# Power_Supply_V4_1.net
KiCad netlist of a schematic drawn in EAGLE
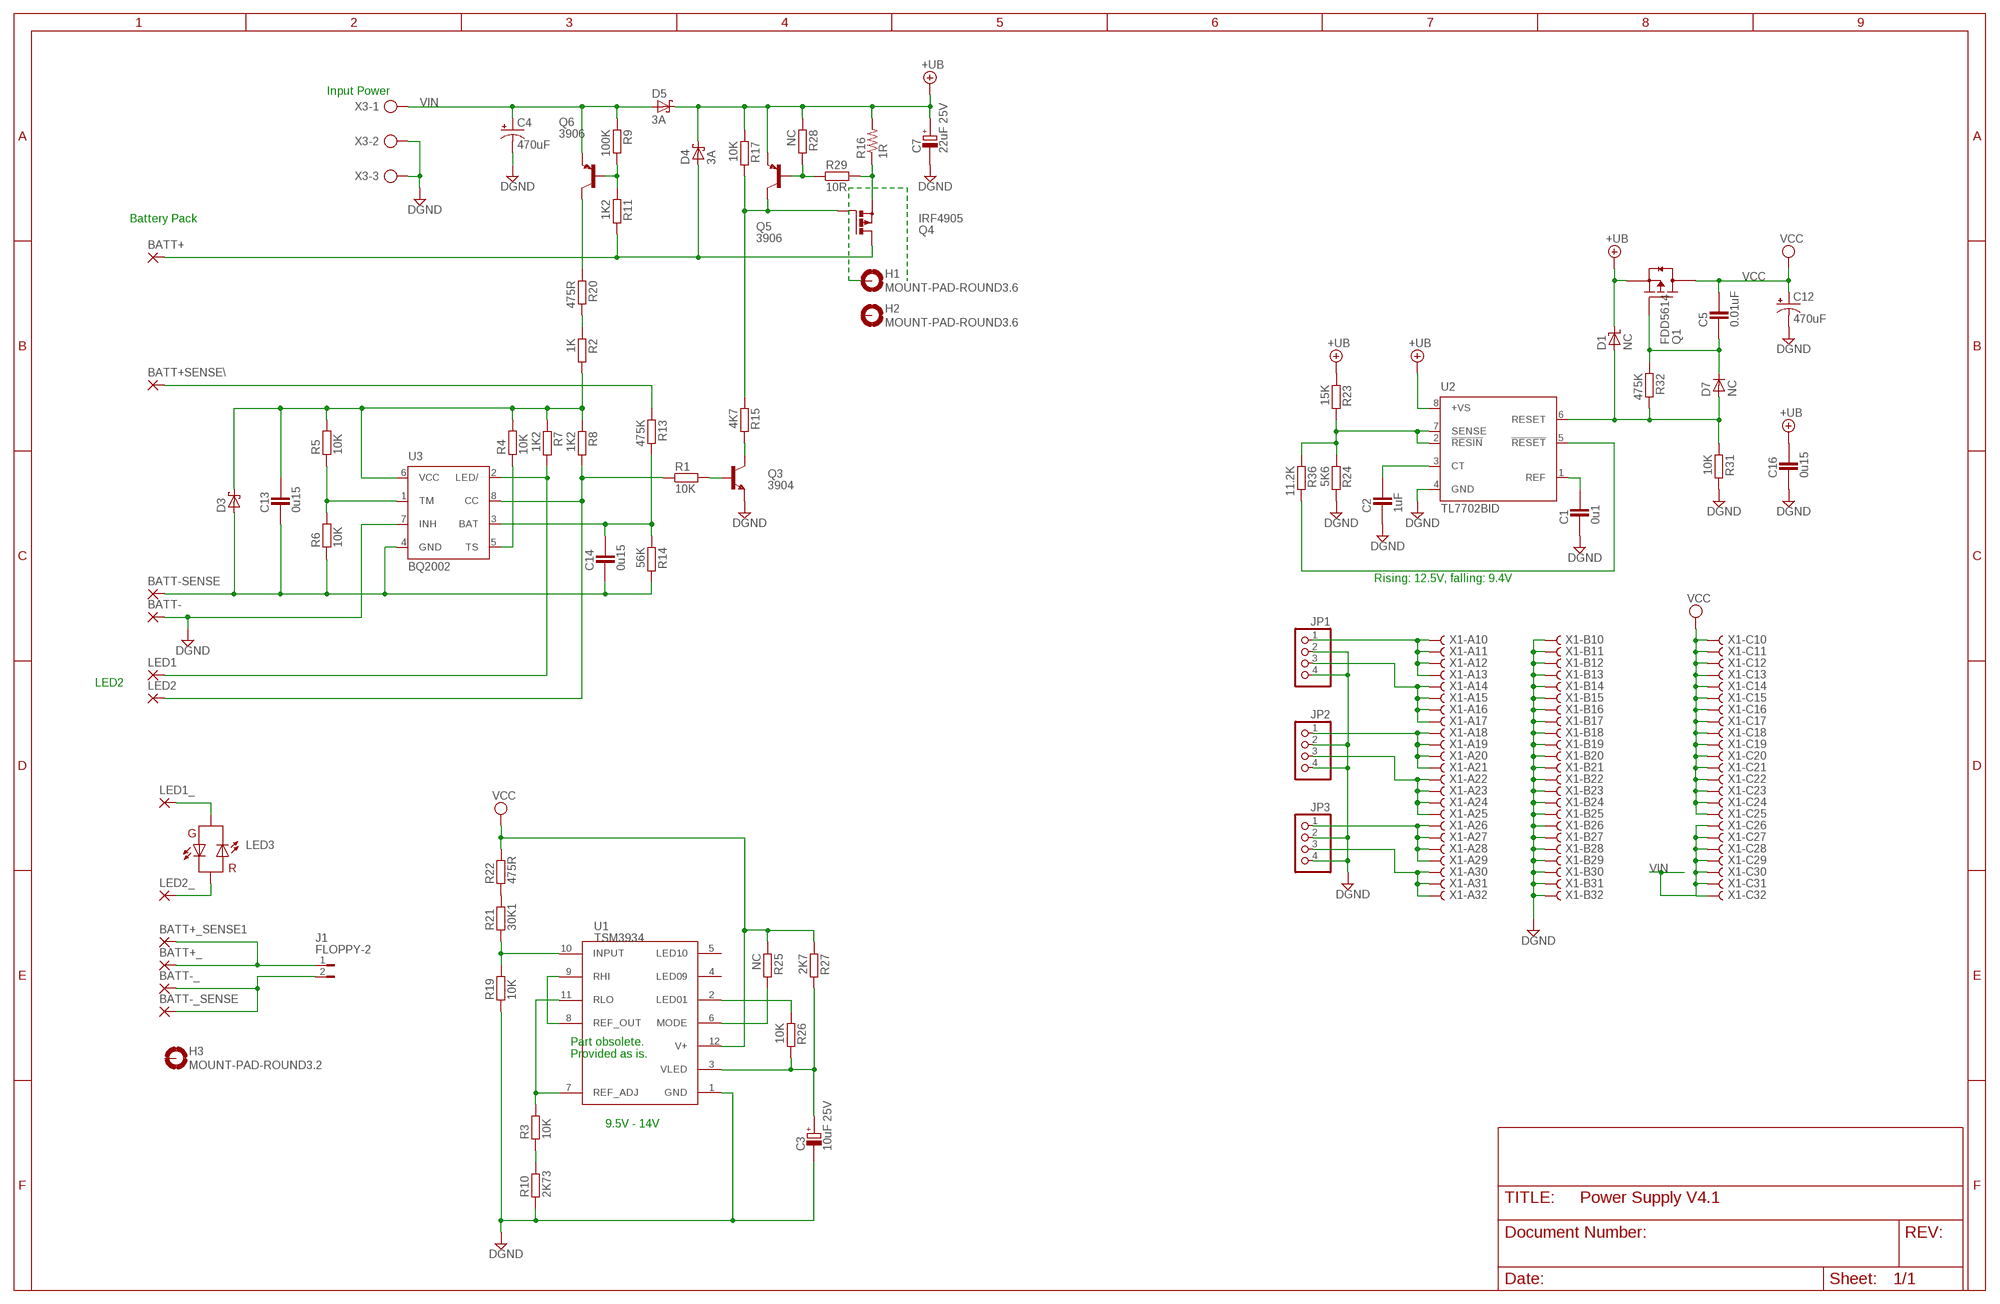
[diagram p0: schematic, sheet 1]

(export (version "E")
  (design (tool "Eeschema 10.0.6"))
  (components
    (comp (ref "BATT+")
      (value "SMD5")
      (footprint "eagle-import:SMD2,54-5,08")
      (libsource (lib "eagle-import") (part "SMD5"))
    )
    (comp (ref "BATT+SENSE\\")
      (value "SMD5")
      (footprint "eagle-import:SMD2,54-5,08")
      (libsource (lib "eagle-import") (part "SMD5"))
    )
    (comp (ref "BATT+_")
      (value "SMD5")
      (footprint "eagle-import:SMD2,54-5,08")
      (libsource (lib "eagle-import") (part "SMD5"))
    )
    (comp (ref "BATT+_SENSE1")
      (value "SMD5")
      (footprint "eagle-import:SMD2,54-5,08")
      (libsource (lib "eagle-import") (part "SMD5"))
    )
    (comp (ref "BATT-")
      (value "SMD5")
      (footprint "eagle-import:SMD2,54-5,08")
      (libsource (lib "eagle-import") (part "SMD5"))
    )
    (comp (ref "BATT-SENSE")
      (value "SMD5")
      (footprint "eagle-import:SMD2,54-5,08")
      (libsource (lib "eagle-import") (part "SMD5"))
    )
    (comp (ref "BATT-_")
      (value "SMD5")
      (footprint "eagle-import:SMD2,54-5,08")
      (libsource (lib "eagle-import") (part "SMD5"))
    )
    (comp (ref "BATT-_SENSE")
      (value "SMD5")
      (footprint "eagle-import:SMD2,54-5,08")
      (libsource (lib "eagle-import") (part "SMD5"))
    )
    (comp (ref "C1")
      (value "0u1")
      (footprint "eagle-import:CAPC1608X92N")
      (libsource (lib "eagle-import") (part "CAPACITOR_0603"))
    )
    (comp (ref "C2")
      (value "1uF")
      (footprint "eagle-import:CAPC1608X92N")
      (libsource (lib "eagle-import") (part "CAPACITOR_0603"))
    )
    (comp (ref "C3")
      (value "10uF 25V")
      (footprint "eagle-import:CAPMP7343X310N")
      (libsource (lib "eagle-import") (part "POLARISED_D_CASE"))
    )
    (comp (ref "C4")
      (value "470uF")
      (footprint "eagle-import:PANASONIC_G")
      (libsource (lib "eagle-import") (part "CAP_POLG"))
    )
    (comp (ref "C5")
      (value "0.01uF")
      (footprint "eagle-import:CAP2012X70N")
      (libsource (lib "eagle-import") (part "CAPACITOR_0805N"))
    )
    (comp (ref "C7")
      (value "22uF 25V")
      (footprint "eagle-import:CAPMP7343X310N")
      (libsource (lib "eagle-import") (part "POLARISED_D_CASE"))
    )
    (comp (ref "C12")
      (value "470uF")
      (footprint "eagle-import:PANASONIC_G")
      (libsource (lib "eagle-import") (part "CAP_POLG"))
    )
    (comp (ref "C13")
      (value "0u15")
      (footprint "eagle-import:CAPC1608X92N")
      (libsource (lib "eagle-import") (part "CAPACITOR_0603"))
    )
    (comp (ref "C14")
      (value "0u15")
      (footprint "eagle-import:CAPC1608X92N")
      (libsource (lib "eagle-import") (part "CAPACITOR_0603"))
    )
    (comp (ref "C16")
      (value "0u15")
      (footprint "eagle-import:CAPC1608X92N")
      (libsource (lib "eagle-import") (part "CAPACITOR_0603"))
    )
    (comp (ref "D1")
      (value "NC")
      (footprint "eagle-import:SOT95P280X135-3N")
      (libsource (lib "eagle-import") (part "ZENER_SOT-23"))
    )
    (comp (ref "D3")
      (value "SCHOTTKY_SOT-23")
      (footprint "eagle-import:SOT95P280X135-3N")
      (libsource (lib "eagle-import") (part "SCHOTTKY_SOT-23"))
    )
    (comp (ref "D4")
      (value "3A")
      (footprint "eagle-import:DIOM7959X265N")
      (libsource (lib "eagle-import") (part "SCHOTTKY_SMC"))
    )
    (comp (ref "D5")
      (value "3A")
      (footprint "eagle-import:DIOM7959X265N")
      (libsource (lib "eagle-import") (part "SCHOTTKY_SMC"))
    )
    (comp (ref "D7")
      (value "NC")
      (footprint "eagle-import:SOT95P280X135-3N")
      (libsource (lib "eagle-import") (part "DIODE_SOT-23"))
    )
    (comp (ref "H1")
      (value "MOUNT-PAD-ROUND3.6")
      (footprint "eagle-import:3,6-PAD")
      (libsource (lib "eagle-import") (part "MOUNT-PAD-ROUND3.6"))
    )
    (comp (ref "H2")
      (value "MOUNT-PAD-ROUND3.6")
      (footprint "eagle-import:3,6-PAD")
      (libsource (lib "eagle-import") (part "MOUNT-PAD-ROUND3.6"))
    )
    (comp (ref "H3")
      (value "MOUNT-PAD-ROUND3.2")
      (footprint "eagle-import:3,2-PAD")
      (libsource (lib "eagle-import") (part "MOUNT-PAD-ROUND3.2"))
    )
    (comp (ref "J1")
      (value "FLOPPY-2")
      (footprint "eagle-import:FLOPPY-2")
      (libsource (lib "eagle-import") (part "FLOPPY-2"))
    )
    (comp (ref "JP1")
      (value "PINHD-1X4_2.54")
      (footprint "eagle-import:1X04")
      (libsource (lib "eagle-import") (part "PINHD-1X4_2.54"))
    )
    (comp (ref "JP2")
      (value "PINHD-1X4_2.54")
      (footprint "eagle-import:1X04")
      (libsource (lib "eagle-import") (part "PINHD-1X4_2.54"))
    )
    (comp (ref "JP3")
      (value "PINHD-1X4_2.54")
      (footprint "eagle-import:1X04")
      (libsource (lib "eagle-import") (part "PINHD-1X4_2.54"))
    )
    (comp (ref "LED1")
      (value "SMD5")
      (footprint "eagle-import:SMD2,54-5,08")
      (libsource (lib "eagle-import") (part "SMD5"))
    )
    (comp (ref "LED1_")
      (value "SMD5")
      (footprint "eagle-import:SMD2,54-5,08")
      (libsource (lib "eagle-import") (part "SMD5"))
    )
    (comp (ref "LED2")
      (value "SMD5")
      (footprint "eagle-import:SMD2,54-5,08")
      (libsource (lib "eagle-import") (part "SMD5"))
    )
    (comp (ref "LED2_")
      (value "SMD5")
      (footprint "eagle-import:SMD2,54-5,08")
      (libsource (lib "eagle-import") (part "SMD5"))
    )
    (comp (ref "LED3")
      (value "DUAL-LED3MM")
      (footprint "eagle-import:LED3MM")
      (libsource (lib "eagle-import") (part "DUAL-LED3MM"))
    )
    (comp (ref "Q1")
      (value "FDD5614")
      (footprint "eagle-import:D-PAK_TO252AA")
      (libsource (lib "eagle-import") (part "MOSFET-PCH_D-PAK"))
    )
    (comp (ref "Q3")
      (value "3904")
      (footprint "eagle-import:SOT95P280X135-3N")
      (libsource (lib "eagle-import") (part "NPN_SOT-23"))
    )
    (comp (ref "Q4")
      (value "IRF4905")
      (footprint "eagle-import:TO220BH")
      (libsource (lib "eagle-import") (part "PMOSFET_PTO220BH"))
    )
    (comp (ref "Q5")
      (value "3906")
      (footprint "eagle-import:SOT95P280X135-3N")
      (libsource (lib "eagle-import") (part "PNP_SOT-23"))
    )
    (comp (ref "Q6")
      (value "3906")
      (footprint "eagle-import:SOT95P280X135-3N")
      (libsource (lib "eagle-import") (part "PNP_SOT-23"))
    )
    (comp (ref "R1")
      (value "10K")
      (footprint "eagle-import:RESC1608X55N")
      (libsource (lib "eagle-import") (part "RESISTOR_0603"))
    )
    (comp (ref "R2")
      (value "1K")
      (footprint "eagle-import:RESC2012X70N")
      (libsource (lib "eagle-import") (part "RESISTOR_0805"))
    )
    (comp (ref "R3")
      (value "10K")
      (footprint "eagle-import:RESC1608X55N")
      (libsource (lib "eagle-import") (part "RESISTOR_0603"))
    )
    (comp (ref "R4")
      (value "10K")
      (footprint "eagle-import:RESC1608X55N")
      (libsource (lib "eagle-import") (part "RESISTOR_0603"))
    )
    (comp (ref "R5")
      (value "10K")
      (footprint "eagle-import:RESC1608X55N")
      (libsource (lib "eagle-import") (part "RESISTOR_0603"))
    )
    (comp (ref "R6")
      (value "10K")
      (footprint "eagle-import:RESC1608X55N")
      (libsource (lib "eagle-import") (part "RESISTOR_0603"))
    )
    (comp (ref "R7")
      (value "1K2")
      (footprint "eagle-import:RESC1608X55N")
      (libsource (lib "eagle-import") (part "RESISTOR_0603"))
    )
    (comp (ref "R8")
      (value "1K2")
      (footprint "eagle-import:RESC1608X55N")
      (libsource (lib "eagle-import") (part "RESISTOR_0603"))
    )
    (comp (ref "R9")
      (value "100K")
      (footprint "eagle-import:RESC1608X55N")
      (libsource (lib "eagle-import") (part "RESISTOR_0603"))
    )
    (comp (ref "R10")
      (value "2K73")
      (footprint "eagle-import:RESC1608X55N")
      (libsource (lib "eagle-import") (part "RESISTOR_0603"))
    )
    (comp (ref "R11")
      (value "1K2")
      (footprint "eagle-import:RESC1608X55N")
      (libsource (lib "eagle-import") (part "RESISTOR_0603"))
    )
    (comp (ref "R13")
      (value "475K")
      (footprint "eagle-import:RESC1608X55N")
      (libsource (lib "eagle-import") (part "RESISTOR_0603"))
    )
    (comp (ref "R14")
      (value "56K")
      (footprint "eagle-import:RESC2012X70N")
      (libsource (lib "eagle-import") (part "RESISTOR_0805"))
    )
    (comp (ref "R15")
      (value "4K7")
      (footprint "eagle-import:RESC1608X55N")
      (libsource (lib "eagle-import") (part "RESISTOR_0603"))
    )
    (comp (ref "R16")
      (value "1R")
      (footprint "eagle-import:0411_12")
      (libsource (lib "eagle-import") (part "R-US_0411/12"))
    )
    (comp (ref "R17")
      (value "10K")
      (footprint "eagle-import:RESC1608X55N")
      (libsource (lib "eagle-import") (part "RESISTOR_0603"))
    )
    (comp (ref "R19")
      (value "10K")
      (footprint "eagle-import:RESC1608X55N")
      (libsource (lib "eagle-import") (part "RESISTOR_0603"))
    )
    (comp (ref "R20")
      (value "475R")
      (footprint "eagle-import:RESC2012X70N")
      (libsource (lib "eagle-import") (part "RESISTOR_0805"))
    )
    (comp (ref "R21")
      (value "30K1")
      (footprint "eagle-import:RESC1608X55N")
      (libsource (lib "eagle-import") (part "RESISTOR_0603"))
    )
    (comp (ref "R22")
      (value "475R")
      (footprint "eagle-import:RESC1608X55N")
      (libsource (lib "eagle-import") (part "RESISTOR_0603"))
    )
    (comp (ref "R23")
      (value "15K")
      (footprint "eagle-import:RESC2012X70N")
      (libsource (lib "eagle-import") (part "RESISTOR_0805"))
    )
    (comp (ref "R24")
      (value "5K6")
      (footprint "eagle-import:RESC2012X70N")
      (libsource (lib "eagle-import") (part "RESISTOR_0805"))
    )
    (comp (ref "R25")
      (value "NC")
      (footprint "eagle-import:RESC1608X55N")
      (libsource (lib "eagle-import") (part "RESISTOR_0603"))
    )
    (comp (ref "R26")
      (value "10K")
      (footprint "eagle-import:RESC1608X55N")
      (libsource (lib "eagle-import") (part "RESISTOR_0603"))
    )
    (comp (ref "R27")
      (value "2K7")
      (footprint "eagle-import:RESC1608X55N")
      (libsource (lib "eagle-import") (part "RESISTOR_0603"))
    )
    (comp (ref "R28")
      (value "NC")
      (footprint "eagle-import:RESC1608X55N")
      (libsource (lib "eagle-import") (part "RESISTOR_0603"))
    )
    (comp (ref "R29")
      (value "10R")
      (footprint "eagle-import:RESC1608X55N")
      (libsource (lib "eagle-import") (part "RESISTOR_0603"))
    )
    (comp (ref "R31")
      (value "10K")
      (footprint "eagle-import:RESC1608X55N")
      (libsource (lib "eagle-import") (part "RESISTOR_0603"))
    )
    (comp (ref "R32")
      (value "475K")
      (footprint "eagle-import:RESC1608X55N")
      (libsource (lib "eagle-import") (part "RESISTOR_0603"))
    )
    (comp (ref "R36")
      (value "11.2K")
      (footprint "eagle-import:RESC1608X55N")
      (libsource (lib "eagle-import") (part "RESISTOR_0603"))
    )
    (comp (ref "U1")
      (value "TSM3934")
      (footprint "eagle-import:TSM3934")
      (libsource (lib "eagle-import") (part "TSM3934"))
    )
    (comp (ref "U2")
      (value "TL7702BID")
      (footprint "eagle-import:SO08")
      (libsource (lib "eagle-import") (part "TL770D02AI"))
    )
    (comp (ref "U3")
      (value "BQ2002")
      (footprint "eagle-import:DIL08")
      (libsource (lib "eagle-import") (part "BQ2002TP"))
    )
    (comp (ref "X1")
      (value "FABC69R")
      (footprint "eagle-import:FABC69R")
      (libsource (lib "eagle-import") (part "FABC69R"))
    )
    (comp (ref "X3")
      (value "AK500/3")
      (footprint "eagle-import:AK500_3")
      (libsource (lib "eagle-import") (part "AK500/3"))
    )
  )
  (nets
    (net (code "1") (name "+UB") (class "Default")
      (node (ref "C16") (pin "2") (pinfunction "2_2") (pintype "passive"))
      (node (ref "C7") (pin "+") (pinfunction "+_+") (pintype "passive"))
      (node (ref "D1") (pin "3") (pinfunction "K_3") (pintype "passive"))
      (node (ref "D4") (pin "K") (pinfunction "K_K") (pintype "passive"))
      (node (ref "D5") (pin "K") (pinfunction "K_K") (pintype "passive"))
      (node (ref "Q1") (pin "3") (pinfunction "S_3") (pintype "passive"))
      (node (ref "Q5") (pin "2") (pinfunction "E_2") (pintype "passive"))
      (node (ref "R16") (pin "2") (pinfunction "2_2") (pintype "passive"))
      (node (ref "R17") (pin "1") (pinfunction "1_1") (pintype "passive"))
      (node (ref "R23") (pin "1") (pinfunction "1_1") (pintype "passive"))
      (node (ref "R28") (pin "1") (pinfunction "1_1") (pintype "passive"))
      (node (ref "U2") (pin "8") (pinfunction "+VS_8") (pintype "input"))
    )
    (net (code "2") (name "/VIN") (class "Default")
      (node (ref "C4") (pin "+") (pinfunction "+_+") (pintype "passive"))
      (node (ref "D5") (pin "A") (pinfunction "A_A") (pintype "passive"))
      (node (ref "Q6") (pin "2") (pinfunction "E_2") (pintype "passive"))
      (node (ref "R9") (pin "1") (pinfunction "1_1") (pintype "passive"))
      (node (ref "X1") (pin "C26") (pinfunction "B_C26") (pintype "passive"))
      (node (ref "X1") (pin "C27") (pinfunction "B_C27") (pintype "passive"))
      (node (ref "X1") (pin "C28") (pinfunction "B_C28") (pintype "passive"))
      (node (ref "X1") (pin "C29") (pinfunction "B_C29") (pintype "passive"))
      (node (ref "X1") (pin "C30") (pinfunction "B_C30") (pintype "passive"))
      (node (ref "X1") (pin "C31") (pinfunction "B_C31") (pintype "passive"))
      (node (ref "X1") (pin "C32") (pinfunction "B_C32") (pintype "passive"))
      (node (ref "X3") (pin "1") (pinfunction "KL_1") (pintype "passive"))
    )
    (net (code "3") (name "DGND") (class "Default")
      (node (ref "BATT-") (pin "1") (pinfunction "P_1") (pintype "passive"))
      (node (ref "C1") (pin "1") (pinfunction "1_1") (pintype "passive"))
      (node (ref "C12") (pin "-") (pinfunction "-_-") (pintype "passive"))
      (node (ref "C16") (pin "1") (pinfunction "1_1") (pintype "passive"))
      (node (ref "C2") (pin "1") (pinfunction "1_1") (pintype "passive"))
      (node (ref "C3") (pin "-") (pinfunction "-_-") (pintype "passive"))
      (node (ref "C4") (pin "-") (pinfunction "-_-") (pintype "passive"))
      (node (ref "C7") (pin "-") (pinfunction "-_-") (pintype "passive"))
      (node (ref "JP1") (pin "2") (pinfunction "2_2") (pintype "passive"))
      (node (ref "JP1") (pin "4") (pinfunction "4_4") (pintype "passive"))
      (node (ref "JP2") (pin "2") (pinfunction "2_2") (pintype "passive"))
      (node (ref "JP2") (pin "4") (pinfunction "4_4") (pintype "passive"))
      (node (ref "JP3") (pin "2") (pinfunction "2_2") (pintype "passive"))
      (node (ref "JP3") (pin "4") (pinfunction "4_4") (pintype "passive"))
      (node (ref "Q3") (pin "2") (pinfunction "E_2") (pintype "passive"))
      (node (ref "R10") (pin "1") (pinfunction "1_1") (pintype "passive"))
      (node (ref "R19") (pin "1") (pinfunction "1_1") (pintype "passive"))
      (node (ref "R24") (pin "2") (pinfunction "2_2") (pintype "passive"))
      (node (ref "R31") (pin "2") (pinfunction "2_2") (pintype "passive"))
      (node (ref "U1") (pin "1") (pinfunction "GND_1") (pintype "power_in"))
      (node (ref "U2") (pin "4") (pinfunction "GND_4") (pintype "power_in"))
      (node (ref "U3") (pin "7") (pinfunction "INH_7") (pintype "input"))
      (node (ref "X1") (pin "B10") (pinfunction "B_B10") (pintype "passive"))
      (node (ref "X1") (pin "B11") (pinfunction "B_B11") (pintype "passive"))
      (node (ref "X1") (pin "B12") (pinfunction "B_B12") (pintype "passive"))
      (node (ref "X1") (pin "B13") (pinfunction "B_B13") (pintype "passive"))
      (node (ref "X1") (pin "B14") (pinfunction "B_B14") (pintype "passive"))
      (node (ref "X1") (pin "B15") (pinfunction "B_B15") (pintype "passive"))
      (node (ref "X1") (pin "B16") (pinfunction "B_B16") (pintype "passive"))
      (node (ref "X1") (pin "B17") (pinfunction "B_B17") (pintype "passive"))
      (node (ref "X1") (pin "B18") (pinfunction "B_B18") (pintype "passive"))
      (node (ref "X1") (pin "B19") (pinfunction "B_B19") (pintype "passive"))
      (node (ref "X1") (pin "B20") (pinfunction "B_B20") (pintype "passive"))
      (node (ref "X1") (pin "B21") (pinfunction "B_B21") (pintype "passive"))
      (node (ref "X1") (pin "B22") (pinfunction "B_B22") (pintype "passive"))
      (node (ref "X1") (pin "B23") (pinfunction "B_B23") (pintype "passive"))
      (node (ref "X1") (pin "B24") (pinfunction "B_B24") (pintype "passive"))
      (node (ref "X1") (pin "B25") (pinfunction "B_B25") (pintype "passive"))
      (node (ref "X1") (pin "B26") (pinfunction "B_B26") (pintype "passive"))
      (node (ref "X1") (pin "B27") (pinfunction "B_B27") (pintype "passive"))
      (node (ref "X1") (pin "B28") (pinfunction "B_B28") (pintype "passive"))
      (node (ref "X1") (pin "B29") (pinfunction "B_B29") (pintype "passive"))
      (node (ref "X1") (pin "B30") (pinfunction "B_B30") (pintype "passive"))
      (node (ref "X1") (pin "B31") (pinfunction "B_B31") (pintype "passive"))
      (node (ref "X1") (pin "B32") (pinfunction "B_B32") (pintype "passive"))
      (node (ref "X3") (pin "2") (pinfunction "KL_2") (pintype "passive"))
      (node (ref "X3") (pin "3") (pinfunction "KL_3") (pintype "passive"))
    )
    (net (code "4") (name "Net-(BATT+-P)") (class "Default")
      (node (ref "BATT+") (pin "1") (pinfunction "P_1") (pintype "passive"))
      (node (ref "D4") (pin "A") (pinfunction "A_A") (pintype "passive"))
      (node (ref "Q4") (pin "D") (pinfunction "D_D") (pintype "passive"))
      (node (ref "R11") (pin "2") (pinfunction "2_2") (pintype "passive"))
    )
    (net (code "5") (name "Net-(BATT+SENSE\\-P)") (class "Default")
      (node (ref "BATT+SENSE\\") (pin "1") (pinfunction "P_1") (pintype "passive"))
      (node (ref "R13") (pin "1") (pinfunction "1_1") (pintype "passive"))
    )
    (net (code "6") (name "Net-(BATT+_-P)") (class "Default")
      (node (ref "BATT+_") (pin "1") (pinfunction "P_1") (pintype "passive"))
      (node (ref "BATT+_SENSE1") (pin "1") (pinfunction "P_1") (pintype "passive"))
      (node (ref "J1") (pin "1") (pinfunction "1_1") (pintype "passive"))
    )
    (net (code "7") (name "Net-(BATT-SENSE-P)") (class "Default")
      (node (ref "BATT-SENSE") (pin "1") (pinfunction "P_1") (pintype "passive"))
      (node (ref "C13") (pin "1") (pinfunction "1_1") (pintype "passive"))
      (node (ref "C14") (pin "1") (pinfunction "1_1") (pintype "passive"))
      (node (ref "D3") (pin "1") (pinfunction "A_1") (pintype "passive"))
      (node (ref "R14") (pin "2") (pinfunction "2_2") (pintype "passive"))
      (node (ref "R6") (pin "1") (pinfunction "1_1") (pintype "passive"))
      (node (ref "U3") (pin "4") (pinfunction "GND_4") (pintype "power_in"))
    )
    (net (code "8") (name "Net-(BATT-_-P)") (class "Default")
      (node (ref "BATT-_") (pin "1") (pinfunction "P_1") (pintype "passive"))
      (node (ref "BATT-_SENSE") (pin "1") (pinfunction "P_1") (pintype "passive"))
      (node (ref "J1") (pin "2") (pinfunction "2_2") (pintype "passive"))
    )
    (net (code "9") (name "Net-(D1-A)") (class "Default")
      (node (ref "D1") (pin "1") (pinfunction "A_1") (pintype "passive"))
      (node (ref "D7") (pin "1") (pinfunction "A_1") (pintype "passive"))
      (node (ref "R31") (pin "1") (pinfunction "1_1") (pintype "passive"))
      (node (ref "R32") (pin "2") (pinfunction "2_2") (pintype "passive"))
      (node (ref "U2") (pin "6") (pinfunction "RESET_6") (pintype "open_collector"))
    )
    (net (code "10") (name "Net-(D3-K)") (class "Default")
      (node (ref "C13") (pin "2") (pinfunction "2_2") (pintype "passive"))
      (node (ref "D3") (pin "3") (pinfunction "K_3") (pintype "passive"))
      (node (ref "R2") (pin "2") (pinfunction "2_2") (pintype "passive"))
      (node (ref "R4") (pin "2") (pinfunction "2_2") (pintype "passive"))
      (node (ref "R5") (pin "2") (pinfunction "2_2") (pintype "passive"))
      (node (ref "R7") (pin "1") (pinfunction "1_1") (pintype "passive"))
      (node (ref "R8") (pin "1") (pinfunction "1_1") (pintype "passive"))
      (node (ref "U3") (pin "6") (pinfunction "VCC_6") (pintype "power_in"))
    )
    (net (code "11") (name "Net-(D7-K)") (class "Default")
      (node (ref "C5") (pin "1") (pinfunction "1_1") (pintype "passive"))
      (node (ref "D7") (pin "3") (pinfunction "K_3") (pintype "passive"))
      (node (ref "Q1") (pin "1") (pinfunction "G_1") (pintype "passive"))
      (node (ref "R32") (pin "1") (pinfunction "1_1") (pintype "passive"))
    )
    (net (code "12") (name "Net-(LED1-P)") (class "Default")
      (node (ref "LED1") (pin "1") (pinfunction "P_1") (pintype "passive"))
      (node (ref "R7") (pin "2") (pinfunction "2_2") (pintype "passive"))
      (node (ref "U3") (pin "2") (pinfunction "LED/_2") (pintype "open_collector"))
    )
    (net (code "13") (name "Net-(LED1_-P)") (class "Default")
      (node (ref "LED1_") (pin "1") (pinfunction "P_1") (pintype "passive"))
      (node (ref "LED3") (pin "A") (pinfunction "A_A") (pintype "passive"))
    )
    (net (code "14") (name "Net-(LED2-P)") (class "Default")
      (node (ref "LED2") (pin "1") (pinfunction "P_1") (pintype "passive"))
      (node (ref "R1") (pin "1") (pinfunction "1_1") (pintype "passive"))
      (node (ref "R8") (pin "2") (pinfunction "2_2") (pintype "passive"))
      (node (ref "U3") (pin "8") (pinfunction "CC_8") (pintype "open_collector"))
    )
    (net (code "15") (name "Net-(LED2_-P)") (class "Default")
      (node (ref "LED2_") (pin "1") (pinfunction "P_1") (pintype "passive"))
      (node (ref "LED3") (pin "K") (pinfunction "C_K") (pintype "passive"))
    )
    (net (code "16") (name "Net-(Q3-B)") (class "Default")
      (node (ref "Q3") (pin "1") (pinfunction "B_1") (pintype "passive"))
      (node (ref "R1") (pin "2") (pinfunction "2_2") (pintype "passive"))
    )
    (net (code "17") (name "Net-(Q3-C)") (class "Default")
      (node (ref "Q3") (pin "3") (pinfunction "C_3") (pintype "passive"))
      (node (ref "R15") (pin "2") (pinfunction "2_2") (pintype "passive"))
    )
    (net (code "18") (name "Net-(Q4-PadS)") (class "Default")
      (node (ref "Q4") (pin "S") (pinfunction "S_S") (pintype "passive"))
      (node (ref "R16") (pin "1") (pinfunction "1_1") (pintype "passive"))
      (node (ref "R29") (pin "2") (pinfunction "2_2") (pintype "passive"))
    )
    (net (code "19") (name "Net-(Q5-B)") (class "Default")
      (node (ref "Q5") (pin "1") (pinfunction "B_1") (pintype "passive"))
      (node (ref "R28") (pin "2") (pinfunction "2_2") (pintype "passive"))
      (node (ref "R29") (pin "1") (pinfunction "1_1") (pintype "passive"))
    )
    (net (code "20") (name "Net-(Q5-C)") (class "Default")
      (node (ref "Q4") (pin "G") (pinfunction "G_G") (pintype "passive"))
      (node (ref "Q5") (pin "3") (pinfunction "C_3") (pintype "passive"))
      (node (ref "R15") (pin "1") (pinfunction "1_1") (pintype "passive"))
      (node (ref "R17") (pin "2") (pinfunction "2_2") (pintype "passive"))
    )
    (net (code "21") (name "Net-(Q6-B)") (class "Default")
      (node (ref "Q6") (pin "1") (pinfunction "B_1") (pintype "passive"))
      (node (ref "R11") (pin "1") (pinfunction "1_1") (pintype "passive"))
      (node (ref "R9") (pin "2") (pinfunction "2_2") (pintype "passive"))
    )
    (net (code "22") (name "Net-(Q6-C)") (class "Default")
      (node (ref "Q6") (pin "3") (pinfunction "C_3") (pintype "passive"))
      (node (ref "R20") (pin "1") (pinfunction "1_1") (pintype "passive"))
    )
    (net (code "23") (name "Net-(R2-Pad1)") (class "Default")
      (node (ref "R2") (pin "1") (pinfunction "1_1") (pintype "passive"))
      (node (ref "R20") (pin "2") (pinfunction "2_2") (pintype "passive"))
    )
    (net (code "24") (name "Net-(R10-Pad2)") (class "Default")
      (node (ref "R10") (pin "2") (pinfunction "2_2") (pintype "passive"))
      (node (ref "R3") (pin "1") (pinfunction "1_1") (pintype "passive"))
    )
    (net (code "25") (name "Net-(R21-Pad2)") (class "Default")
      (node (ref "R21") (pin "2") (pinfunction "2_2") (pintype "passive"))
      (node (ref "R22") (pin "1") (pinfunction "1_1") (pintype "passive"))
    )
    (net (code "26") (name "Net-(U1-INPUT)") (class "Default")
      (node (ref "R19") (pin "2") (pinfunction "2_2") (pintype "passive"))
      (node (ref "R21") (pin "1") (pinfunction "1_1") (pintype "passive"))
      (node (ref "U1") (pin "10") (pinfunction "INPUT_10") (pintype "input"))
    )
    (net (code "27") (name "Net-(U1-LED01)") (class "Default")
      (node (ref "R26") (pin "1") (pinfunction "1_1") (pintype "passive"))
      (node (ref "U1") (pin "2") (pinfunction "LED01_2") (pintype "output"))
    )
    (net (code "28") (name "Net-(U1-MODE)") (class "Default")
      (node (ref "R25") (pin "2") (pinfunction "2_2") (pintype "passive"))
      (node (ref "U1") (pin "6") (pinfunction "MODE_6") (pintype "input"))
    )
    (net (code "29") (name "Net-(U1-REF_ADJ)") (class "Default")
      (node (ref "R3") (pin "2") (pinfunction "2_2") (pintype "passive"))
      (node (ref "U1") (pin "11") (pinfunction "RLO_11") (pintype "input"))
      (node (ref "U1") (pin "7") (pinfunction "REF_ADJ_7") (pintype "input"))
    )
    (net (code "30") (name "Net-(U1-REF_OUT)") (class "Default")
      (node (ref "U1") (pin "8") (pinfunction "REF_OUT_8") (pintype "output"))
      (node (ref "U1") (pin "9") (pinfunction "RHI_9") (pintype "input"))
    )
    (net (code "31") (name "Net-(U1-VLED)") (class "Default")
      (node (ref "C3") (pin "+") (pinfunction "+_+") (pintype "passive"))
      (node (ref "R26") (pin "2") (pinfunction "2_2") (pintype "passive"))
      (node (ref "R27") (pin "2") (pinfunction "2_2") (pintype "passive"))
      (node (ref "U1") (pin "3") (pinfunction "VLED_3") (pintype "power_in"))
    )
    (net (code "32") (name "Net-(U2-CT)") (class "Default")
      (node (ref "C2") (pin "2") (pinfunction "2_2") (pintype "passive"))
      (node (ref "U2") (pin "3") (pinfunction "CT_3") (pintype "input"))
    )
    (net (code "33") (name "Net-(U2-REF)") (class "Default")
      (node (ref "C1") (pin "2") (pinfunction "2_2") (pintype "passive"))
      (node (ref "U2") (pin "1") (pinfunction "REF_1") (pintype "input"))
    )
    (net (code "34") (name "Net-(U2-SENSE)") (class "Default")
      (node (ref "R23") (pin "2") (pinfunction "2_2") (pintype "passive"))
      (node (ref "R24") (pin "1") (pinfunction "1_1") (pintype "passive"))
      (node (ref "R36") (pin "1") (pinfunction "1_1") (pintype "passive"))
      (node (ref "U2") (pin "2") (pinfunction "~{RESIN}_2") (pintype "input"))
      (node (ref "U2") (pin "7") (pinfunction "SENSE_7") (pintype "input"))
    )
    (net (code "35") (name "Net-(U2-~{RESET})") (class "Default")
      (node (ref "R36") (pin "2") (pinfunction "2_2") (pintype "passive"))
      (node (ref "U2") (pin "5") (pinfunction "~{RESET}_5") (pintype "open_collector"))
    )
    (net (code "36") (name "Net-(U3-BAT)") (class "Default")
      (node (ref "C14") (pin "2") (pinfunction "2_2") (pintype "passive"))
      (node (ref "R13") (pin "2") (pinfunction "2_2") (pintype "passive"))
      (node (ref "R14") (pin "1") (pinfunction "1_1") (pintype "passive"))
      (node (ref "U3") (pin "3") (pinfunction "BAT_3") (pintype "input"))
    )
    (net (code "37") (name "Net-(U3-TM)") (class "Default")
      (node (ref "R5") (pin "1") (pinfunction "1_1") (pintype "passive"))
      (node (ref "R6") (pin "2") (pinfunction "2_2") (pintype "passive"))
      (node (ref "U3") (pin "1") (pinfunction "TM_1") (pintype "input"))
    )
    (net (code "38") (name "Net-(U3-TS)") (class "Default")
      (node (ref "R4") (pin "1") (pinfunction "1_1") (pintype "passive"))
      (node (ref "U3") (pin "5") (pinfunction "TS_5") (pintype "input"))
    )
    (net (code "39") (name "Net-(X1A-B)") (class "Default")
      (node (ref "JP1") (pin "1") (pinfunction "1_1") (pintype "passive"))
      (node (ref "X1") (pin "A10") (pinfunction "B_A10") (pintype "passive"))
      (node (ref "X1") (pin "A11") (pinfunction "B_A11") (pintype "passive"))
      (node (ref "X1") (pin "A12") (pinfunction "B_A12") (pintype "passive"))
      (node (ref "X1") (pin "A13") (pinfunction "B_A13") (pintype "passive"))
    )
    (net (code "40") (name "Net-(X1E-B)") (class "Default")
      (node (ref "JP1") (pin "3") (pinfunction "3_3") (pintype "passive"))
      (node (ref "X1") (pin "A14") (pinfunction "B_A14") (pintype "passive"))
      (node (ref "X1") (pin "A15") (pinfunction "B_A15") (pintype "passive"))
      (node (ref "X1") (pin "A16") (pinfunction "B_A16") (pintype "passive"))
      (node (ref "X1") (pin "A17") (pinfunction "B_A17") (pintype "passive"))
    )
    (net (code "41") (name "Net-(X1I-B)") (class "Default")
      (node (ref "JP2") (pin "1") (pinfunction "1_1") (pintype "passive"))
      (node (ref "X1") (pin "A18") (pinfunction "B_A18") (pintype "passive"))
      (node (ref "X1") (pin "A19") (pinfunction "B_A19") (pintype "passive"))
      (node (ref "X1") (pin "A20") (pinfunction "B_A20") (pintype "passive"))
      (node (ref "X1") (pin "A21") (pinfunction "B_A21") (pintype "passive"))
    )
    (net (code "42") (name "Net-(X1M-B)") (class "Default")
      (node (ref "JP2") (pin "3") (pinfunction "3_3") (pintype "passive"))
      (node (ref "X1") (pin "A22") (pinfunction "B_A22") (pintype "passive"))
      (node (ref "X1") (pin "A23") (pinfunction "B_A23") (pintype "passive"))
      (node (ref "X1") (pin "A24") (pinfunction "B_A24") (pintype "passive"))
      (node (ref "X1") (pin "A25") (pinfunction "B_A25") (pintype "passive"))
    )
    (net (code "43") (name "Net-(X1Q-B)") (class "Default")
      (node (ref "JP3") (pin "1") (pinfunction "1_1") (pintype "passive"))
      (node (ref "X1") (pin "A26") (pinfunction "B_A26") (pintype "passive"))
      (node (ref "X1") (pin "A27") (pinfunction "B_A27") (pintype "passive"))
      (node (ref "X1") (pin "A28") (pinfunction "B_A28") (pintype "passive"))
      (node (ref "X1") (pin "A29") (pinfunction "B_A29") (pintype "passive"))
    )
    (net (code "44") (name "Net-(X1U-B)") (class "Default")
      (node (ref "JP3") (pin "3") (pinfunction "3_3") (pintype "passive"))
      (node (ref "X1") (pin "A30") (pinfunction "B_A30") (pintype "passive"))
      (node (ref "X1") (pin "A31") (pinfunction "B_A31") (pintype "passive"))
      (node (ref "X1") (pin "A32") (pinfunction "B_A32") (pintype "passive"))
    )
    (net (code "45") (name "VCC") (class "Default")
      (node (ref "C12") (pin "+") (pinfunction "+_+") (pintype "passive"))
      (node (ref "C5") (pin "2") (pinfunction "2_2") (pintype "passive"))
      (node (ref "Q1") (pin "4") (pinfunction "D_4") (pintype "passive"))
      (node (ref "R22") (pin "2") (pinfunction "2_2") (pintype "passive"))
      (node (ref "R25") (pin "1") (pinfunction "1_1") (pintype "passive"))
      (node (ref "R27") (pin "1") (pinfunction "1_1") (pintype "passive"))
      (node (ref "U1") (pin "12") (pinfunction "V+_12") (pintype "power_in"))
      (node (ref "X1") (pin "C10") (pinfunction "B_C10") (pintype "passive"))
      (node (ref "X1") (pin "C11") (pinfunction "B_C11") (pintype "passive"))
      (node (ref "X1") (pin "C12") (pinfunction "B_C12") (pintype "passive"))
      (node (ref "X1") (pin "C13") (pinfunction "B_C13") (pintype "passive"))
      (node (ref "X1") (pin "C14") (pinfunction "B_C14") (pintype "passive"))
      (node (ref "X1") (pin "C15") (pinfunction "B_C15") (pintype "passive"))
      (node (ref "X1") (pin "C16") (pinfunction "B_C16") (pintype "passive"))
      (node (ref "X1") (pin "C17") (pinfunction "B_C17") (pintype "passive"))
      (node (ref "X1") (pin "C18") (pinfunction "B_C18") (pintype "passive"))
      (node (ref "X1") (pin "C19") (pinfunction "B_C19") (pintype "passive"))
      (node (ref "X1") (pin "C20") (pinfunction "B_C20") (pintype "passive"))
      (node (ref "X1") (pin "C21") (pinfunction "B_C21") (pintype "passive"))
      (node (ref "X1") (pin "C22") (pinfunction "B_C22") (pintype "passive"))
      (node (ref "X1") (pin "C23") (pinfunction "B_C23") (pintype "passive"))
      (node (ref "X1") (pin "C24") (pinfunction "B_C24") (pintype "passive"))
      (node (ref "X1") (pin "C25") (pinfunction "B_C25") (pintype "passive"))
    )
    (net (code "46") (name "unconnected-(H1-MOUNT-PadB3,6)") (class "Default")
      (node (ref "H1") (pin "B3,6") (pinfunction "MOUNT_B3,6") (pintype "passive"))
    )
    (net (code "47") (name "unconnected-(H2-MOUNT-PadB3,6)") (class "Default")
      (node (ref "H2") (pin "B3,6") (pinfunction "MOUNT_B3,6") (pintype "passive"))
    )
    (net (code "48") (name "unconnected-(H3-MOUNT-PadB3,2)") (class "Default")
      (node (ref "H3") (pin "B3,2") (pinfunction "MOUNT_B3,2") (pintype "passive"))
    )
    (net (code "49") (name "unconnected-(U1-LED09-Pad4)") (class "Default")
      (node (ref "U1") (pin "4") (pinfunction "LED09_4") (pintype "output"))
    )
    (net (code "50") (name "unconnected-(U1-LED10-Pad5)") (class "Default")
      (node (ref "U1") (pin "5") (pinfunction "LED10_5") (pintype "output"))
    )
  )
)
